# MCUConn.net
KiCad netlist of a schematic drawn in Altium Designer
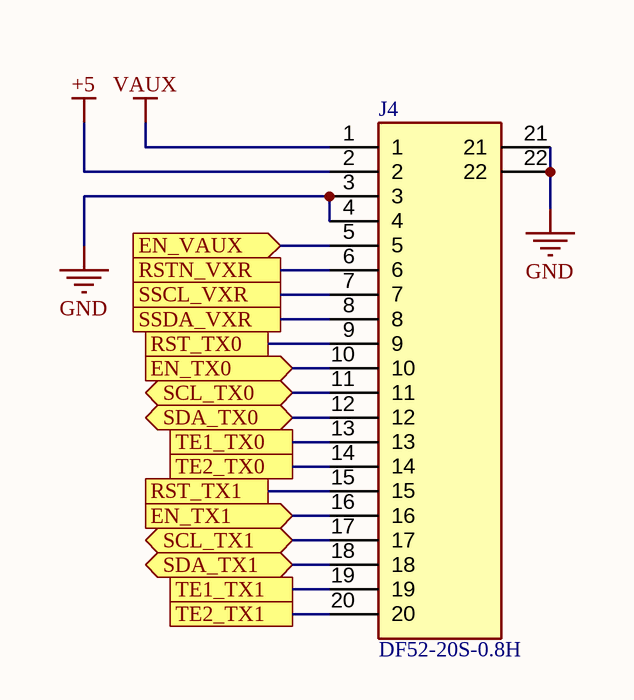
[diagram p0: MCUConn.SchDoc]

(export (version "E")
  (design (tool "Eeschema 10.0.6"))
  (components
    (comp (ref "J4")
      (value "DF52-20S-0.8H")
      (footprint "SamacSys:DF5220S08H")
      (description "Connector")
      (libsource (lib "*") (part "DF52-20S-0.8H"))
    )
  )
  (nets
    (net (code "1") (name "+5") (class "Default")
      (node (ref "J4") (pin "2") (pinfunction "2_2") (pintype "passive"))
    )
    (net (code "2") (name "/EN_TX0") (class "Default")
      (node (ref "J4") (pin "10") (pinfunction "10_10") (pintype "passive"))
    )
    (net (code "3") (name "/EN_TX1") (class "Default")
      (node (ref "J4") (pin "16") (pinfunction "16_16") (pintype "passive"))
    )
    (net (code "4") (name "/EN_VAUX") (class "Default")
      (node (ref "J4") (pin "5") (pinfunction "5_5") (pintype "passive"))
    )
    (net (code "5") (name "/RSTN_VXR") (class "Default")
      (node (ref "J4") (pin "6") (pinfunction "6_6") (pintype "passive"))
    )
    (net (code "6") (name "/RST_TX0") (class "Default")
      (node (ref "J4") (pin "9") (pinfunction "9_9") (pintype "passive"))
    )
    (net (code "7") (name "/RST_TX1") (class "Default")
      (node (ref "J4") (pin "15") (pinfunction "15_15") (pintype "passive"))
    )
    (net (code "8") (name "/SCL_TX0") (class "Default")
      (node (ref "J4") (pin "11") (pinfunction "11_11") (pintype "passive"))
    )
    (net (code "9") (name "/SCL_TX1") (class "Default")
      (node (ref "J4") (pin "17") (pinfunction "17_17") (pintype "passive"))
    )
    (net (code "10") (name "/SDA_TX0") (class "Default")
      (node (ref "J4") (pin "12") (pinfunction "12_12") (pintype "passive"))
    )
    (net (code "11") (name "/SDA_TX1") (class "Default")
      (node (ref "J4") (pin "18") (pinfunction "18_18") (pintype "passive"))
    )
    (net (code "12") (name "/SSCL_VXR") (class "Default")
      (node (ref "J4") (pin "7") (pinfunction "7_7") (pintype "passive"))
    )
    (net (code "13") (name "/SSDA_VXR") (class "Default")
      (node (ref "J4") (pin "8") (pinfunction "8_8") (pintype "passive"))
    )
    (net (code "14") (name "/TE1_TX0") (class "Default")
      (node (ref "J4") (pin "13") (pinfunction "13_13") (pintype "passive"))
    )
    (net (code "15") (name "/TE1_TX1") (class "Default")
      (node (ref "J4") (pin "19") (pinfunction "19_19") (pintype "passive"))
    )
    (net (code "16") (name "/TE2_TX0") (class "Default")
      (node (ref "J4") (pin "14") (pinfunction "14_14") (pintype "passive"))
    )
    (net (code "17") (name "/TE2_TX1") (class "Default")
      (node (ref "J4") (pin "20") (pinfunction "20_20") (pintype "passive"))
    )
    (net (code "18") (name "GND") (class "Default")
      (node (ref "J4") (pin "21") (pinfunction "21_21") (pintype "passive"))
      (node (ref "J4") (pin "22") (pinfunction "22_22") (pintype "passive"))
      (node (ref "J4") (pin "3") (pinfunction "3_3") (pintype "passive"))
      (node (ref "J4") (pin "4") (pinfunction "4_4") (pintype "passive"))
    )
    (net (code "19") (name "VAUX") (class "Default")
      (node (ref "J4") (pin "1") (pinfunction "1_1") (pintype "passive"))
    )
  )
)
